# S1_-_POWER.net
KiCad netlist of a schematic drawn in Altium Designer
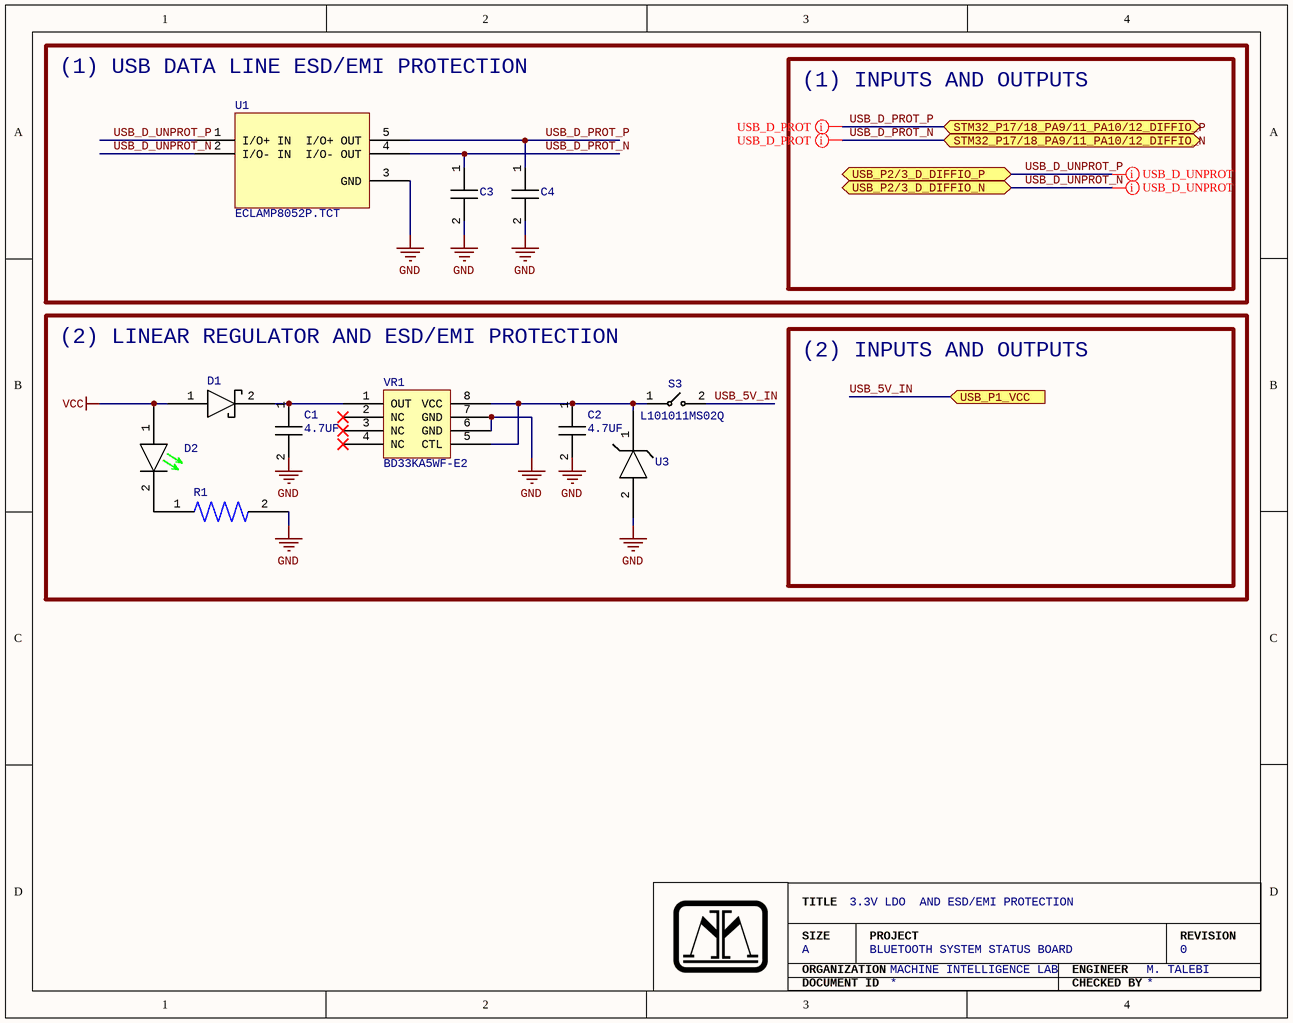
[diagram p0: S1 - POWER.SchDoc]

(export (version "E")
  (design (tool "Eeschema 10.0.6"))
  (components
    (comp (ref "C1")
      (value "4.7UF")
      (footprint "TMK212AB7475KG-T")
      (description "CAP CER 4.7UF 25V X7R 0805")
      (fields (field (name "TOLERANCE") "±10%"))
      (libsource (lib "Master") (part "TMK212AB7475KG-T"))
    )
    (comp (ref "C2")
      (value "4.7UF")
      (footprint "TMK212AB7475KG-T")
      (description "CAP CER 4.7UF 25V X7R 0805")
      (fields (field (name "TOLERANCE") "±10%"))
      (libsource (lib "Master") (part "TMK212AB7475KG-T"))
    )
    (comp (ref "C3")
      (value "CC0603JRNPO8BN470")
      (footprint "CC0603JRNPO8BN470")
      (description "CAP CER 47PF 25V NPO 0603")
      (fields (field (name "TOLERANCE") "±5%"))
      (libsource (lib "Master") (part "CC0603JRNPO8BN470"))
    )
    (comp (ref "C4")
      (value "CC0603JRNPO8BN470")
      (footprint "CC0603JRNPO8BN470")
      (description "CAP CER 47PF 25V NPO 0603")
      (fields (field (name "TOLERANCE") "±5%"))
      (libsource (lib "Master") (part "CC0603JRNPO8BN470"))
    )
    (comp (ref "D1")
      (value "NRVB120VLSFT1G")
      (footprint "SODFL360X98-2N")
      (description "DIODE SCHOTTKY 20V 1A SOD123")
      (libsource (lib "Master") (part "NRVB120VLSFT1G"))
    )
    (comp (ref "D2")
      (value "151031VS06000")
      (footprint "151031VS06000")
      (description "LED GREEN DIFFUSED 3MM ROUND T/H")
      (libsource (lib "Master") (part "151031VS06000"))
    )
    (comp (ref "R1")
      (value "Y162440R0000B9R")
      (footprint "Y162440R0000B9R")
      (description "RES SMD 40 OHM 0.1% 1/5W 0805")
      (fields (field (name "TOLERANCE") "±0.1%"))
      (libsource (lib "Master") (part "Y162440R0000B9R"))
    )
    (comp (ref "S3")
      (value "L101011MS02Q")
      (footprint "L101011MS02Q")
      (description "SWITCH SLIDE SPST 4A 125V")
      (libsource (lib "Master") (part "L101011MS02Q"))
    )
    (comp (ref "U1")
      (value "ECLAMP8052P.TCT")
      (footprint "ECLAMP8052P.TCT")
      (description "CMC 2LN SMD ESD AEC-Q100")
      (libsource (lib "Master") (part "ECLAMP8052P.TCT"))
    )
    (comp (ref "U3")
      (value "UCLAMP0571P.TNT")
      (footprint "UCLAMP0571P.TNT")
      (description "TVS DIODE 5V 15V SGP1610N2")
      (libsource (lib "Master") (part "UCLAMP0571P.TNT"))
    )
    (comp (ref "VR1")
      (value "BD33KA5WF-E2")
      (footprint "BD33KA5WF-E2")
      (description "IC REG LINEAR 3.3V 500MA 8SOP")
      (libsource (lib "Master") (part "BD33KA5WF-E2"))
    )
  )
  (nets
    (net (code "1") (name "/USB_5V_IN") (class "Default")
      (node (ref "S3") (pin "2") (pinfunction "2_2") (pintype "passive"))
    )
    (net (code "2") (name "/USB_D_PROT_N") (class "Default")
      (node (ref "C3") (pin "1") (pinfunction "1_1") (pintype "passive"))
      (node (ref "U1") (pin "4") (pinfunction "I/O-_OUT_4") (pintype "passive"))
    )
    (net (code "3") (name "/USB_D_PROT_P") (class "Default")
      (node (ref "C4") (pin "1") (pinfunction "1_1") (pintype "passive"))
      (node (ref "U1") (pin "5") (pinfunction "I/O+_OUT_5") (pintype "passive"))
    )
    (net (code "4") (name "/USB_D_UNPROT_N") (class "Default")
      (node (ref "U1") (pin "2") (pinfunction "I/O-_IN_2") (pintype "passive"))
    )
    (net (code "5") (name "/USB_D_UNPROT_P") (class "Default")
      (node (ref "U1") (pin "1") (pinfunction "I/O+_IN_1") (pintype "passive"))
    )
    (net (code "6") (name "GND") (class "Default")
      (node (ref "C1") (pin "2") (pinfunction "2_2") (pintype "passive"))
      (node (ref "C2") (pin "2") (pinfunction "2_2") (pintype "passive"))
      (node (ref "C3") (pin "2") (pinfunction "2_2") (pintype "passive"))
      (node (ref "C4") (pin "2") (pinfunction "2_2") (pintype "passive"))
      (node (ref "R1") (pin "2") (pinfunction "2_2") (pintype "passive"))
      (node (ref "U1") (pin "3") (pinfunction "GND_3") (pintype "passive"))
      (node (ref "U3") (pin "2") (pinfunction "2_2") (pintype "passive"))
      (node (ref "VR1") (pin "6") (pinfunction "GND_6") (pintype "passive"))
      (node (ref "VR1") (pin "7") (pinfunction "GND_7") (pintype "passive"))
    )
    (net (code "7") (name "Net-(D1-+)") (class "Default")
      (node (ref "C1") (pin "1") (pinfunction "1_1") (pintype "passive"))
      (node (ref "D1") (pin "2") (pinfunction "+_2") (pintype "passive"))
      (node (ref "VR1") (pin "1") (pinfunction "OUT_1") (pintype "passive"))
    )
    (net (code "8") (name "Net-(D2-+)") (class "Default")
      (node (ref "D2") (pin "2") (pinfunction "+_2") (pintype "passive"))
      (node (ref "R1") (pin "1") (pinfunction "1_1") (pintype "passive"))
    )
    (net (code "9") (name "Net-(VR1-CTL)") (class "Default")
      (node (ref "C2") (pin "1") (pinfunction "1_1") (pintype "passive"))
      (node (ref "S3") (pin "1") (pinfunction "1_1") (pintype "passive"))
      (node (ref "U3") (pin "1") (pinfunction "1_1") (pintype "passive"))
      (node (ref "VR1") (pin "5") (pinfunction "CTL_5") (pintype "passive"))
      (node (ref "VR1") (pin "8") (pinfunction "VCC_8") (pintype "passive"))
    )
    (net (code "10") (name "VCC") (class "Default")
      (node (ref "D1") (pin "1") (pinfunction "-_1") (pintype "passive"))
      (node (ref "D2") (pin "1") (pinfunction "-_1") (pintype "passive"))
    )
    (net (code "11") (name "unconnected-(VR1-NC-Pad2)") (class "Default")
      (node (ref "VR1") (pin "2") (pinfunction "NC_2") (pintype "passive+no_connect"))
    )
    (net (code "12") (name "unconnected-(VR1-NC-Pad3)") (class "Default")
      (node (ref "VR1") (pin "3") (pinfunction "NC_3") (pintype "passive+no_connect"))
    )
    (net (code "13") (name "unconnected-(VR1-NC-Pad4)") (class "Default")
      (node (ref "VR1") (pin "4") (pinfunction "NC_4") (pintype "passive+no_connect"))
    )
  )
)
